# drv.net
KiCad netlist of a schematic drawn in Altium Designer
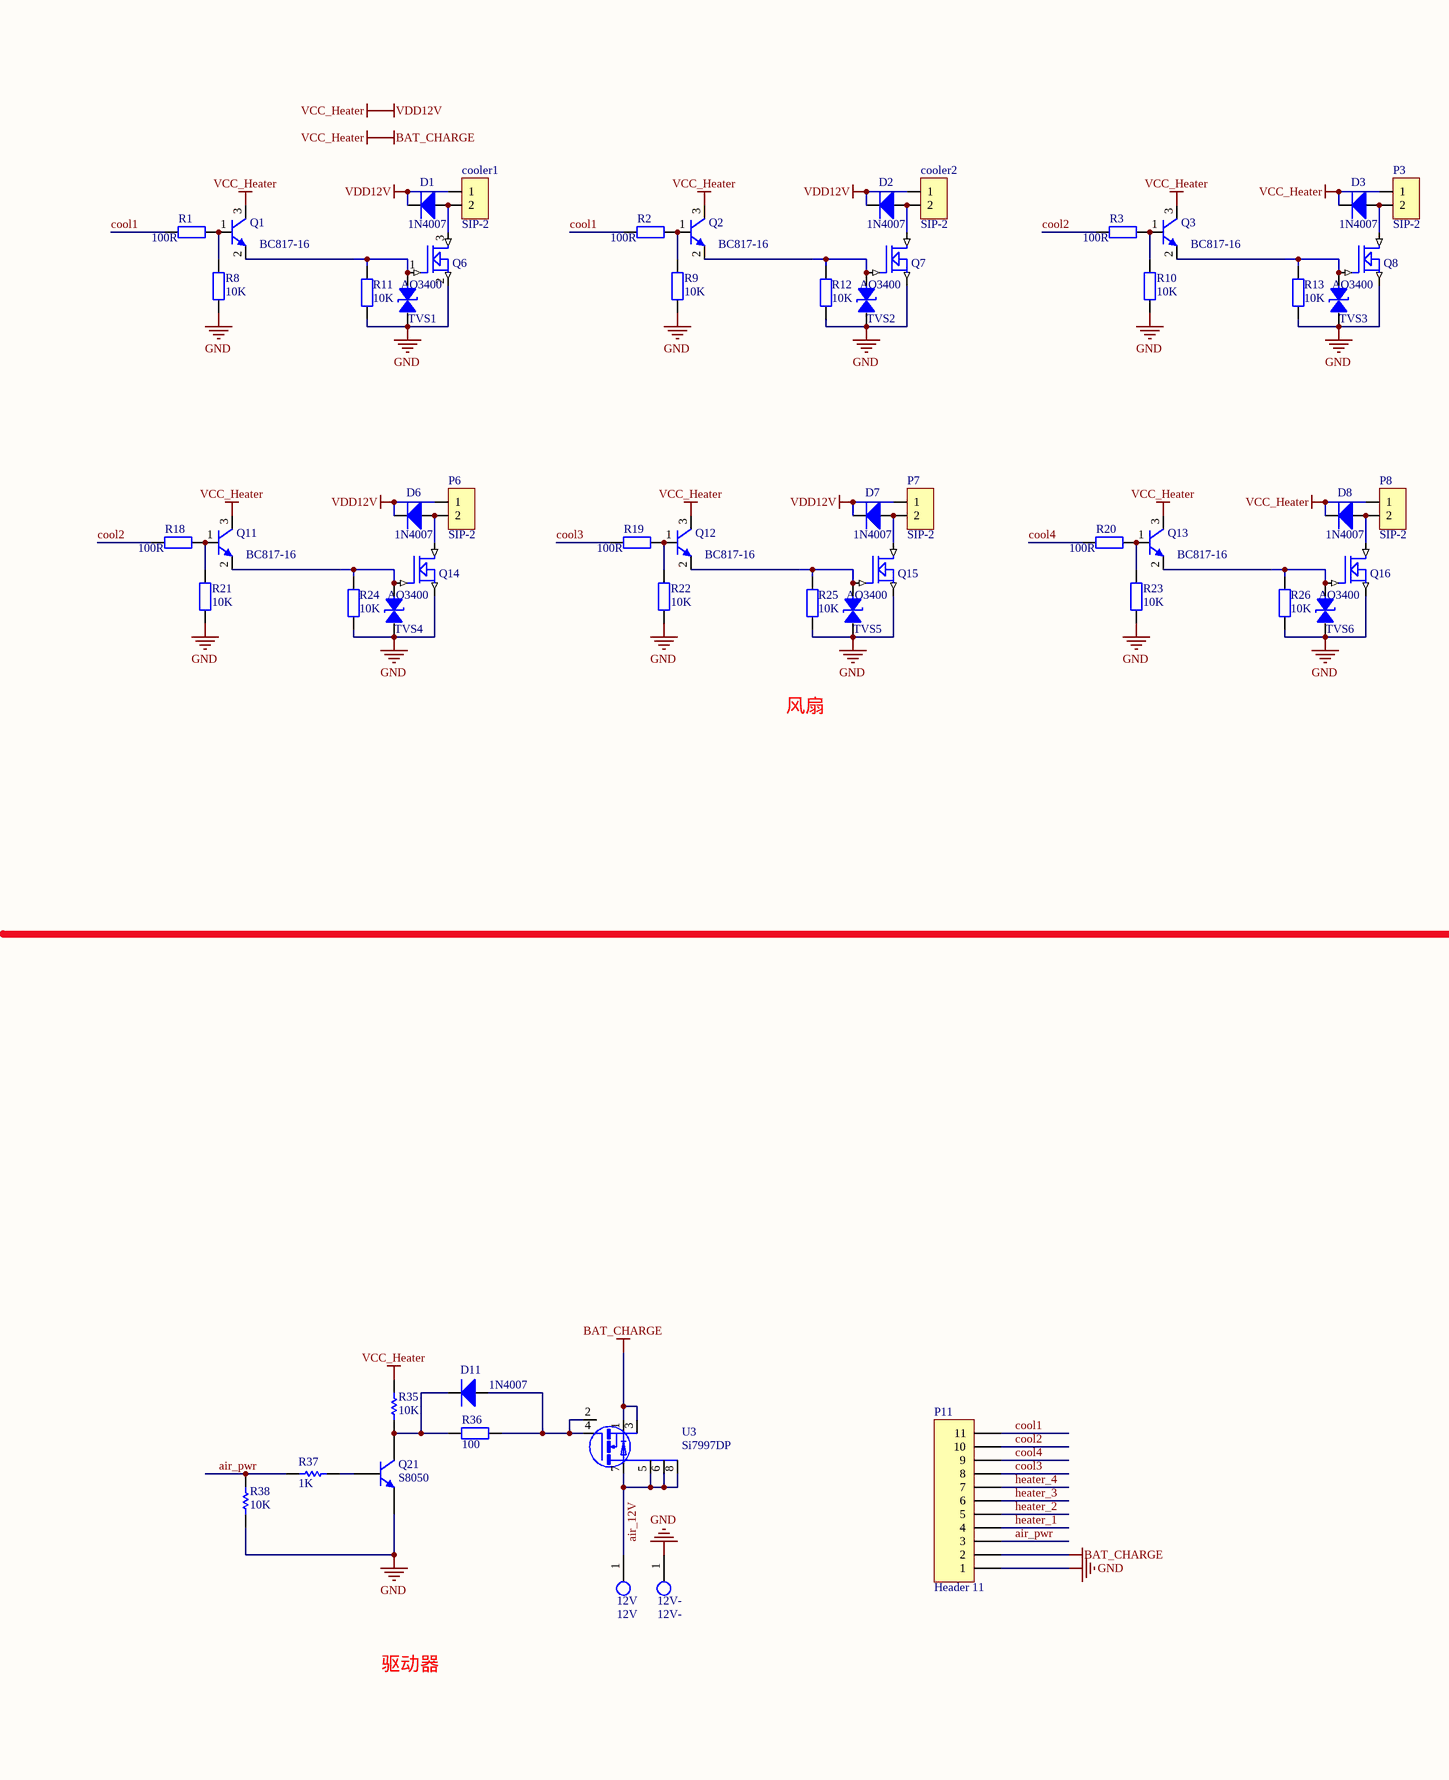
[diagram p0: drv.SchDoc, left]
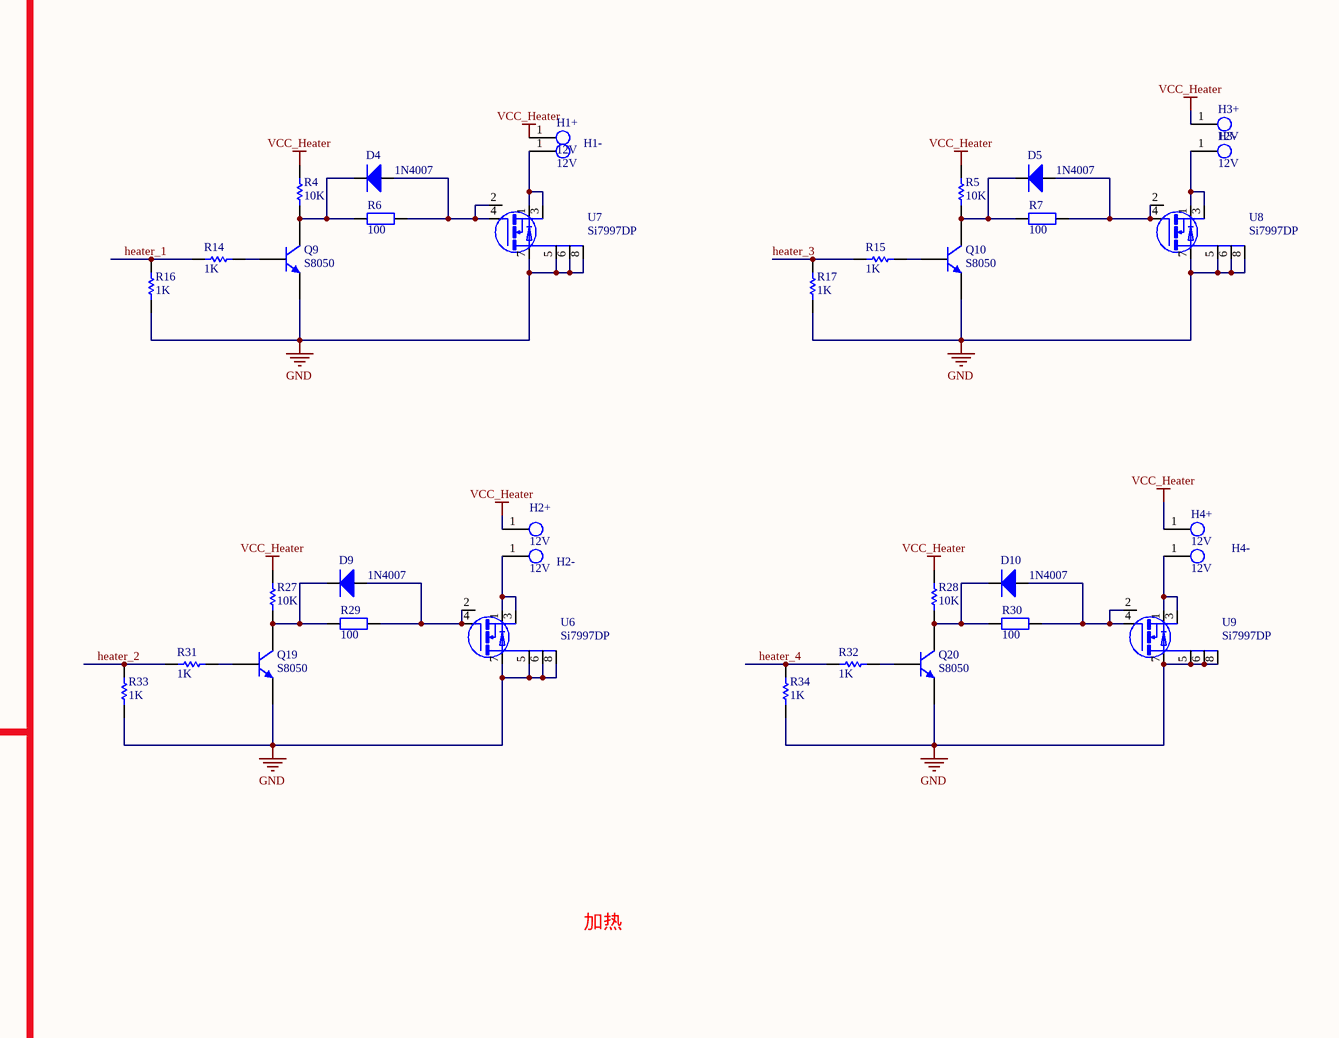
[diagram p1: drv.SchDoc, right]

(export (version "E")
  (design (tool "Eeschema 10.0.6"))
  (components
    (comp (ref "12V") (value "12V") (footprint "FIX-4.5") (libsource (lib "Schlib_20110825") (part "TP")))
    (comp (ref "12V-") (value "12V-") (footprint "FIX-4.5") (libsource (lib "Schlib_20110825") (part "TP")))
    (comp (ref "cooler1")
      (value "SIP-2")
      (footprint "SIP-2A")
      (description "XH2.54 2P 立贴")
      (libsource (lib "XiaoyI") (part "SIP-2"))
    )
    (comp (ref "cooler2")
      (value "SIP-2")
      (footprint "SIP-2A")
      (description "XH2.54 2P 立贴")
      (libsource (lib "XiaoyI") (part "SIP-2"))
    )
    (comp (ref "D1")
      (value "1N4007")
      (footprint "DO-214-AC")
      (description "贴片二极管")
      (libsource (lib "XiaoyI") (part "DIODE2"))
    )
    (comp (ref "D2")
      (value "1N4007")
      (footprint "DO-214-AC")
      (description "贴片二极管")
      (libsource (lib "XiaoyI") (part "DIODE2"))
    )
    (comp (ref "D3")
      (value "1N4007")
      (footprint "DO-214-AC")
      (description "贴片二极管")
      (libsource (lib "XiaoyI") (part "DIODE2"))
    )
    (comp (ref "D4")
      (value "1N4007")
      (footprint "DO-214-AC")
      (description "贴片二极管")
      (libsource (lib "XiaoyI") (part "DIODE2"))
    )
    (comp (ref "D5")
      (value "1N4007")
      (footprint "DO-214-AC")
      (description "贴片二极管")
      (libsource (lib "XiaoyI") (part "DIODE2"))
    )
    (comp (ref "D6")
      (value "1N4007")
      (footprint "DO-214-AC")
      (description "贴片二极管")
      (libsource (lib "XiaoyI") (part "DIODE2"))
    )
    (comp (ref "D7")
      (value "1N4007")
      (footprint "DO-214-AC")
      (description "贴片二极管")
      (libsource (lib "XiaoyI") (part "DIODE2"))
    )
    (comp (ref "D8")
      (value "1N4007")
      (footprint "DO-214-AC")
      (description "贴片二极管")
      (libsource (lib "XiaoyI") (part "DIODE2"))
    )
    (comp (ref "D9")
      (value "1N4007")
      (footprint "DO-214-AC")
      (description "贴片二极管")
      (libsource (lib "XiaoyI") (part "DIODE2"))
    )
    (comp (ref "D10")
      (value "1N4007")
      (footprint "DO-214-AC")
      (description "贴片二极管")
      (libsource (lib "XiaoyI") (part "DIODE2"))
    )
    (comp (ref "D11")
      (value "1N4007")
      (footprint "DO-214-AC")
      (description "贴片二极管")
      (libsource (lib "XiaoyI") (part "DIODE2"))
    )
    (comp (ref "H1+") (value "12V") (footprint "FIX-4.5") (libsource (lib "Schlib_20110825") (part "TP")))
    (comp (ref "H1-") (value "12V") (footprint "FIX-4.5") (libsource (lib "Schlib_20110825") (part "TP")))
    (comp (ref "H2+") (value "12V") (footprint "FIX-4.5") (libsource (lib "Schlib_20110825") (part "TP")))
    (comp (ref "H2-") (value "12V") (footprint "FIX-4.5") (libsource (lib "Schlib_20110825") (part "TP")))
    (comp (ref "H3+") (value "12V") (footprint "FIX-4.5") (libsource (lib "Schlib_20110825") (part "TP")))
    (comp (ref "H3-") (value "12V") (footprint "FIX-4.5") (libsource (lib "Schlib_20110825") (part "TP")))
    (comp (ref "H4+") (value "12V") (footprint "FIX-4.5") (libsource (lib "Schlib_20110825") (part "TP")))
    (comp (ref "H4-") (value "12V") (footprint "FIX-4.5") (libsource (lib "Schlib_20110825") (part "TP")))
    (comp (ref "P3")
      (value "SIP-2")
      (footprint "SIP-2A")
      (description "XH2.54 2P 立贴")
      (libsource (lib "XiaoyI") (part "SIP-2"))
    )
    (comp (ref "P6")
      (value "SIP-2")
      (footprint "SIP-2A")
      (description "XH2.54 2P 立贴")
      (libsource (lib "XiaoyI") (part "SIP-2"))
    )
    (comp (ref "P7")
      (value "SIP-2")
      (footprint "SIP-2A")
      (description "XH2.54 2P 立贴")
      (libsource (lib "XiaoyI") (part "SIP-2"))
    )
    (comp (ref "P8")
      (value "SIP-2")
      (footprint "SIP-2A")
      (description "XH2.54 2P 立贴")
      (libsource (lib "XiaoyI") (part "SIP-2"))
    )
    (comp (ref "P11")
      (value "Header 11")
      (footprint "12X2MMZ")
      (description "Header, 11-Pin")
      (fields (field (name "PUBLISHER") "Altium Limited"))
      (libsource (lib "Miscellaneous Connectors") (part "Header 11"))
    )
    (comp (ref "Q1")
      (value "BC817-16")
      (footprint "SOT23-3")
      (description "三极管")
      (libsource (lib "XiaoyI") (part "NPN-1"))
    )
    (comp (ref "Q2")
      (value "BC817-16")
      (footprint "SOT23-3")
      (description "三极管")
      (libsource (lib "XiaoyI") (part "NPN-1"))
    )
    (comp (ref "Q3")
      (value "BC817-16")
      (footprint "SOT23-3")
      (description "三极管")
      (libsource (lib "XiaoyI") (part "NPN-1"))
    )
    (comp (ref "Q6")
      (value "AO3400")
      (footprint "SOT23-3")
      (description "MOSFET N")
      (libsource (lib "") (part "MOSFET N_1"))
    )
    (comp (ref "Q7")
      (value "AO3400")
      (footprint "SOT23-3")
      (description "MOSFET N")
      (libsource (lib "XiaoyI") (part "MOSFET N"))
    )
    (comp (ref "Q8")
      (value "AO3400")
      (footprint "SOT23-3")
      (description "MOSFET N")
      (libsource (lib "XiaoyI") (part "MOSFET N"))
    )
    (comp (ref "Q9")
      (value "S8050")
      (footprint "SOT23-3")
      (description "NPN Bipolar Transistor")
      (fields (field (name "PUBLISHER") "Altium Limited"))
      (libsource (lib "Miscellaneous Devices") (part "NPN"))
    )
    (comp (ref "Q10")
      (value "S8050")
      (footprint "SOT23-3")
      (description "NPN Bipolar Transistor")
      (fields (field (name "PUBLISHER") "Altium Limited"))
      (libsource (lib "Miscellaneous Devices") (part "NPN"))
    )
    (comp (ref "Q11")
      (value "BC817-16")
      (footprint "SOT23-3")
      (description "三极管")
      (libsource (lib "XiaoyI") (part "NPN-1"))
    )
    (comp (ref "Q12")
      (value "BC817-16")
      (footprint "SOT23-3")
      (description "三极管")
      (libsource (lib "XiaoyI") (part "NPN-1"))
    )
    (comp (ref "Q13")
      (value "BC817-16")
      (footprint "SOT23-3")
      (description "三极管")
      (libsource (lib "XiaoyI") (part "NPN-1"))
    )
    (comp (ref "Q14")
      (value "AO3400")
      (footprint "SOT23-3")
      (description "MOSFET N")
      (libsource (lib "XiaoyI") (part "MOSFET N"))
    )
    (comp (ref "Q15")
      (value "AO3400")
      (footprint "SOT23-3")
      (description "MOSFET N")
      (libsource (lib "XiaoyI") (part "MOSFET N"))
    )
    (comp (ref "Q16")
      (value "AO3400")
      (footprint "SOT23-3")
      (description "MOSFET N")
      (libsource (lib "XiaoyI") (part "MOSFET N"))
    )
    (comp (ref "Q19")
      (value "S8050")
      (footprint "SOT23-3")
      (description "NPN Bipolar Transistor")
      (fields (field (name "PUBLISHER") "Altium Limited"))
      (libsource (lib "Miscellaneous Devices") (part "NPN"))
    )
    (comp (ref "Q20")
      (value "S8050")
      (footprint "SOT23-3")
      (description "NPN Bipolar Transistor")
      (fields (field (name "PUBLISHER") "Altium Limited"))
      (libsource (lib "Miscellaneous Devices") (part "NPN"))
    )
    (comp (ref "Q21")
      (value "S8050")
      (footprint "SOT23-3")
      (description "NPN Bipolar Transistor")
      (fields (field (name "PUBLISHER") "Altium Limited"))
      (libsource (lib "Miscellaneous Devices") (part "NPN"))
    )
    (comp (ref "R1")
      (value "100R")
      (footprint "0603R")
      (description "贴片电阻 5%")
      (libsource (lib "XiaoyI") (part "RES-SOP"))
    )
    (comp (ref "R2")
      (value "100R")
      (footprint "0603R")
      (description "贴片电阻 5%")
      (libsource (lib "XiaoyI") (part "RES-SOP"))
    )
    (comp (ref "R3")
      (value "100R")
      (footprint "0603R")
      (description "贴片电阻 5%")
      (libsource (lib "XiaoyI") (part "RES-SOP"))
    )
    (comp (ref "R4")
      (value "10K")
      (footprint "0603R")
      (description "Resistor")
      (fields (field (name "PUBLISHER") "Altium Limited"))
      (libsource (lib "Miscellaneous Devices") (part "Res1"))
    )
    (comp (ref "R5")
      (value "10K")
      (footprint "0603R")
      (description "Resistor")
      (fields (field (name "PUBLISHER") "Altium Limited"))
      (libsource (lib "Miscellaneous Devices") (part "Res1"))
    )
    (comp (ref "R6")
      (value "100")
      (footprint "0603R")
      (description "贴片电阻 5%")
      (libsource (lib "") (part "RES-SOP_1"))
    )
    (comp (ref "R7")
      (value "100")
      (footprint "0603R")
      (description "贴片电阻 5%")
      (libsource (lib "") (part "RES-SOP_1"))
    )
    (comp (ref "R8")
      (value "10K")
      (footprint "0603R")
      (description "贴片电阻 5%")
      (libsource (lib "") (part "RES-SOP_3"))
    )
    (comp (ref "R9")
      (value "10K")
      (footprint "0603R")
      (description "贴片电阻 5%")
      (libsource (lib "") (part "RES-SOP_3"))
    )
    (comp (ref "R10")
      (value "10K")
      (footprint "0603R")
      (description "贴片电阻 5%")
      (libsource (lib "") (part "RES-SOP_3"))
    )
    (comp (ref "R11")
      (value "10K")
      (footprint "0603R")
      (description "贴片电阻 5%")
      (libsource (lib "") (part "RES-SOP_2"))
    )
    (comp (ref "R12")
      (value "10K")
      (footprint "0603R")
      (description "贴片电阻 5%")
      (libsource (lib "") (part "RES-SOP_2"))
    )
    (comp (ref "R13")
      (value "10K")
      (footprint "0603R")
      (description "贴片电阻 5%")
      (libsource (lib "") (part "RES-SOP_2"))
    )
    (comp (ref "R14")
      (value "1K")
      (footprint "0603R")
      (description "Resistor")
      (fields (field (name "PUBLISHER") "Altium Limited"))
      (libsource (lib "Miscellaneous Devices") (part "Res1"))
    )
    (comp (ref "R15")
      (value "1K")
      (footprint "0603R")
      (description "Resistor")
      (fields (field (name "PUBLISHER") "Altium Limited"))
      (libsource (lib "Miscellaneous Devices") (part "Res1"))
    )
    (comp (ref "R16")
      (value "1K")
      (footprint "0603R")
      (description "Resistor")
      (fields (field (name "PUBLISHER") "Altium Limited"))
      (libsource (lib "Miscellaneous Devices") (part "Res1"))
    )
    (comp (ref "R17")
      (value "1K")
      (footprint "0603R")
      (description "Resistor")
      (fields (field (name "PUBLISHER") "Altium Limited"))
      (libsource (lib "Miscellaneous Devices") (part "Res1"))
    )
    (comp (ref "R18")
      (value "100R")
      (footprint "0603R")
      (description "贴片电阻 5%")
      (libsource (lib "XiaoyI") (part "RES-SOP"))
    )
    (comp (ref "R19")
      (value "100R")
      (footprint "0603R")
      (description "贴片电阻 5%")
      (libsource (lib "XiaoyI") (part "RES-SOP"))
    )
    (comp (ref "R20")
      (value "100R")
      (footprint "0603R")
      (description "贴片电阻 5%")
      (libsource (lib "XiaoyI") (part "RES-SOP"))
    )
    (comp (ref "R21")
      (value "10K")
      (footprint "0603R")
      (description "贴片电阻 5%")
      (libsource (lib "") (part "RES-SOP_3"))
    )
    (comp (ref "R22")
      (value "10K")
      (footprint "0603R")
      (description "贴片电阻 5%")
      (libsource (lib "") (part "RES-SOP_3"))
    )
    (comp (ref "R23")
      (value "10K")
      (footprint "0603R")
      (description "贴片电阻 5%")
      (libsource (lib "") (part "RES-SOP_3"))
    )
    (comp (ref "R24")
      (value "10K")
      (footprint "0603R")
      (description "贴片电阻 5%")
      (libsource (lib "") (part "RES-SOP_2"))
    )
    (comp (ref "R25")
      (value "10K")
      (footprint "0603R")
      (description "贴片电阻 5%")
      (libsource (lib "") (part "RES-SOP_2"))
    )
    (comp (ref "R26")
      (value "10K")
      (footprint "0603R")
      (description "贴片电阻 5%")
      (libsource (lib "") (part "RES-SOP_2"))
    )
    (comp (ref "R27")
      (value "10K")
      (footprint "0603R")
      (description "Resistor")
      (fields (field (name "PUBLISHER") "Altium Limited"))
      (libsource (lib "Miscellaneous Devices") (part "Res1"))
    )
    (comp (ref "R28")
      (value "10K")
      (footprint "0603R")
      (description "Resistor")
      (fields (field (name "PUBLISHER") "Altium Limited"))
      (libsource (lib "Miscellaneous Devices") (part "Res1"))
    )
    (comp (ref "R29")
      (value "100")
      (footprint "0603R")
      (description "贴片电阻 5%")
      (libsource (lib "") (part "RES-SOP_1"))
    )
    (comp (ref "R30")
      (value "100")
      (footprint "0603R")
      (description "贴片电阻 5%")
      (libsource (lib "") (part "RES-SOP_1"))
    )
    (comp (ref "R31")
      (value "1K")
      (footprint "0603R")
      (description "Resistor")
      (fields (field (name "PUBLISHER") "Altium Limited"))
      (libsource (lib "Miscellaneous Devices") (part "Res1"))
    )
    (comp (ref "R32")
      (value "1K")
      (footprint "0603R")
      (description "Resistor")
      (fields (field (name "PUBLISHER") "Altium Limited"))
      (libsource (lib "Miscellaneous Devices") (part "Res1"))
    )
    (comp (ref "R33")
      (value "1K")
      (footprint "0603R")
      (description "Resistor")
      (fields (field (name "PUBLISHER") "Altium Limited"))
      (libsource (lib "Miscellaneous Devices") (part "Res1"))
    )
    (comp (ref "R34")
      (value "1K")
      (footprint "0603R")
      (description "Resistor")
      (fields (field (name "PUBLISHER") "Altium Limited"))
      (libsource (lib "Miscellaneous Devices") (part "Res1"))
    )
    (comp (ref "R35")
      (value "10K")
      (footprint "0603R")
      (description "Resistor")
      (fields (field (name "PUBLISHER") "Altium Limited"))
      (libsource (lib "Miscellaneous Devices") (part "Res1"))
    )
    (comp (ref "R36")
      (value "100")
      (footprint "0603R")
      (description "贴片电阻 5%")
      (libsource (lib "") (part "RES-SOP_1"))
    )
    (comp (ref "R37")
      (value "1K")
      (footprint "0603R")
      (description "Resistor")
      (fields (field (name "PUBLISHER") "Altium Limited"))
      (libsource (lib "Miscellaneous Devices") (part "Res1"))
    )
    (comp (ref "R38")
      (value "10K")
      (footprint "0603R")
      (description "Resistor")
      (fields (field (name "PUBLISHER") "Altium Limited"))
      (libsource (lib "Miscellaneous Devices") (part "Res1"))
    )
    (comp (ref "TVS1")
      (value "ESD5Z5.0CT1G")
      (footprint "SOD-523")
      (description "TVS")
      (libsource (lib "XiaoyI") (part "TVS-1"))
    )
    (comp (ref "TVS2")
      (value "ESD5Z5.0CT1G")
      (footprint "SOD-523")
      (description "TVS")
      (libsource (lib "XiaoyI") (part "TVS-1"))
    )
    (comp (ref "TVS3")
      (value "ESD5Z5.0CT1G")
      (footprint "SOD-523")
      (description "TVS")
      (libsource (lib "XiaoyI") (part "TVS-1"))
    )
    (comp (ref "TVS4")
      (value "ESD5Z5.0CT1G")
      (footprint "SOD-523")
      (description "TVS")
      (libsource (lib "XiaoyI") (part "TVS-1"))
    )
    (comp (ref "TVS5")
      (value "ESD5Z5.0CT1G")
      (footprint "SOD-523")
      (description "TVS")
      (libsource (lib "XiaoyI") (part "TVS-1"))
    )
    (comp (ref "TVS6")
      (value "ESD5Z5.0CT1G")
      (footprint "SOD-523")
      (description "TVS")
      (libsource (lib "XiaoyI") (part "TVS-1"))
    )
    (comp (ref "U3")
      (value "Si7997DP")
      (footprint "PowerPAK SO-8")
      (description "Sia430DJ")
      (libsource (lib "Schlib_20110825") (part "Si7997DP"))
    )
    (comp (ref "U6")
      (value "Si7997DP")
      (footprint "PowerPAK SO-8")
      (description "Sia430DJ")
      (libsource (lib "Schlib_20110825") (part "Si7997DP"))
    )
    (comp (ref "U7")
      (value "Si7997DP")
      (footprint "PowerPAK SO-8")
      (description "Sia430DJ")
      (libsource (lib "Schlib_20110825") (part "Si7997DP"))
    )
    (comp (ref "U8")
      (value "Si7997DP")
      (footprint "PowerPAK SO-8")
      (description "Sia430DJ")
      (libsource (lib "Schlib_20110825") (part "Si7997DP"))
    )
    (comp (ref "U9")
      (value "Si7997DP")
      (footprint "PowerPAK SO-8")
      (description "Sia430DJ")
      (libsource (lib "Schlib_20110825") (part "Si7997DP"))
    )
  )
  (nets
    (net (code "1") (name "/air_12V") (class "Default")
      (node (ref "12V") (pin "1") (pintype "passive"))
      (node (ref "U3") (pin "5") (pinfunction "D_5") (pintype "passive"))
      (node (ref "U3") (pin "6") (pinfunction "D_6") (pintype "passive"))
      (node (ref "U3") (pin "7") (pinfunction "D_7") (pintype "passive"))
      (node (ref "U3") (pin "8") (pinfunction "D_8") (pintype "passive"))
    )
    (net (code "2") (name "/air_pwr") (class "Default")
      (node (ref "P11") (pin "3") (pinfunction "3_3") (pintype "passive"))
      (node (ref "R37") (pin "2") (pinfunction "2_2") (pintype "passive"))
      (node (ref "R38") (pin "1") (pinfunction "1_1") (pintype "passive"))
    )
    (net (code "3") (name "/cool1") (class "Default")
      (node (ref "P11") (pin "11") (pinfunction "11_11") (pintype "passive"))
      (node (ref "R1") (pin "2") (pinfunction "2_2") (pintype "passive"))
      (node (ref "R2") (pin "2") (pinfunction "2_2") (pintype "passive"))
    )
    (net (code "4") (name "/cool2") (class "Default")
      (node (ref "P11") (pin "10") (pinfunction "10_10") (pintype "passive"))
      (node (ref "R18") (pin "2") (pinfunction "2_2") (pintype "passive"))
      (node (ref "R3") (pin "2") (pinfunction "2_2") (pintype "passive"))
    )
    (net (code "5") (name "/cool3") (class "Default")
      (node (ref "P11") (pin "8") (pinfunction "8_8") (pintype "passive"))
      (node (ref "R19") (pin "2") (pinfunction "2_2") (pintype "passive"))
    )
    (net (code "6") (name "/cool4") (class "Default")
      (node (ref "P11") (pin "9") (pinfunction "9_9") (pintype "passive"))
      (node (ref "R20") (pin "2") (pinfunction "2_2") (pintype "passive"))
    )
    (net (code "7") (name "/heater_1") (class "Default")
      (node (ref "P11") (pin "4") (pinfunction "4_4") (pintype "passive"))
      (node (ref "R14") (pin "2") (pinfunction "2_2") (pintype "passive"))
      (node (ref "R16") (pin "1") (pinfunction "1_1") (pintype "passive"))
    )
    (net (code "8") (name "/heater_2") (class "Default")
      (node (ref "P11") (pin "5") (pinfunction "5_5") (pintype "passive"))
      (node (ref "R31") (pin "2") (pinfunction "2_2") (pintype "passive"))
      (node (ref "R33") (pin "1") (pinfunction "1_1") (pintype "passive"))
    )
    (net (code "9") (name "/heater_3") (class "Default")
      (node (ref "P11") (pin "6") (pinfunction "6_6") (pintype "passive"))
      (node (ref "R15") (pin "2") (pinfunction "2_2") (pintype "passive"))
      (node (ref "R17") (pin "1") (pinfunction "1_1") (pintype "passive"))
    )
    (net (code "10") (name "/heater_4") (class "Default")
      (node (ref "P11") (pin "7") (pinfunction "7_7") (pintype "passive"))
      (node (ref "R32") (pin "2") (pinfunction "2_2") (pintype "passive"))
      (node (ref "R34") (pin "1") (pinfunction "1_1") (pintype "passive"))
    )
    (net (code "11") (name "BAT_CHARGE") (class "Default")
      (node (ref "D1") (pin "2") (pinfunction "K_2") (pintype "passive"))
      (node (ref "D2") (pin "2") (pinfunction "K_2") (pintype "passive"))
      (node (ref "D3") (pin "2") (pinfunction "K_2") (pintype "passive"))
      (node (ref "D6") (pin "2") (pinfunction "K_2") (pintype "passive"))
      (node (ref "D7") (pin "2") (pinfunction "K_2") (pintype "passive"))
      (node (ref "D8") (pin "2") (pinfunction "K_2") (pintype "passive"))
      (node (ref "H1+") (pin "1") (pintype "passive"))
      (node (ref "H2+") (pin "1") (pintype "passive"))
      (node (ref "H3+") (pin "1") (pintype "passive"))
      (node (ref "H4+") (pin "1") (pintype "passive"))
      (node (ref "P11") (pin "2") (pinfunction "2_2") (pintype "passive"))
      (node (ref "P3") (pin "1") (pinfunction "1_1") (pintype "passive"))
      (node (ref "P6") (pin "1") (pinfunction "1_1") (pintype "passive"))
      (node (ref "P7") (pin "1") (pinfunction "1_1") (pintype "passive"))
      (node (ref "P8") (pin "1") (pinfunction "1_1") (pintype "passive"))
      (node (ref "Q1") (pin "3") (pinfunction "C_3") (pintype "passive"))
      (node (ref "Q11") (pin "3") (pinfunction "C_3") (pintype "passive"))
      (node (ref "Q12") (pin "3") (pinfunction "C_3") (pintype "passive"))
      (node (ref "Q13") (pin "3") (pinfunction "C_3") (pintype "passive"))
      (node (ref "Q2") (pin "3") (pinfunction "C_3") (pintype "passive"))
      (node (ref "Q3") (pin "3") (pinfunction "C_3") (pintype "passive"))
      (node (ref "R27") (pin "2") (pinfunction "2_2") (pintype "passive"))
      (node (ref "R28") (pin "2") (pinfunction "2_2") (pintype "passive"))
      (node (ref "R35") (pin "2") (pinfunction "2_2") (pintype "passive"))
      (node (ref "R4") (pin "2") (pinfunction "2_2") (pintype "passive"))
      (node (ref "R5") (pin "2") (pinfunction "2_2") (pintype "passive"))
      (node (ref "U3") (pin "1") (pinfunction "S_1") (pintype "passive"))
      (node (ref "U3") (pin "3") (pinfunction "S_3") (pintype "passive"))
      (node (ref "cooler1") (pin "1") (pinfunction "1_1") (pintype "passive"))
      (node (ref "cooler2") (pin "1") (pinfunction "1_1") (pintype "passive"))
    )
    (net (code "12") (name "GND") (class "Default")
      (node (ref "12V-") (pin "1") (pintype "passive"))
      (node (ref "P11") (pin "1") (pinfunction "1_1") (pintype "passive"))
      (node (ref "Q10") (pin "2") (pinfunction "E_2") (pintype "passive"))
      (node (ref "Q14") (pin "2") (pinfunction "S_2") (pintype "output"))
      (node (ref "Q15") (pin "2") (pinfunction "S_2") (pintype "output"))
      (node (ref "Q16") (pin "2") (pinfunction "S_2") (pintype "output"))
      (node (ref "Q19") (pin "2") (pinfunction "E_2") (pintype "passive"))
      (node (ref "Q20") (pin "2") (pinfunction "E_2") (pintype "passive"))
      (node (ref "Q21") (pin "2") (pinfunction "E_2") (pintype "passive"))
      (node (ref "Q6") (pin "2") (pinfunction "S_2") (pintype "output"))
      (node (ref "Q7") (pin "2") (pinfunction "S_2") (pintype "output"))
      (node (ref "Q8") (pin "2") (pinfunction "S_2") (pintype "output"))
      (node (ref "Q9") (pin "2") (pinfunction "E_2") (pintype "passive"))
      (node (ref "R10") (pin "1") (pinfunction "1_1") (pintype "passive"))
      (node (ref "R11") (pin "2") (pinfunction "2_2") (pintype "passive"))
      (node (ref "R12") (pin "2") (pinfunction "2_2") (pintype "passive"))
      (node (ref "R13") (pin "2") (pinfunction "2_2") (pintype "passive"))
      (node (ref "R16") (pin "2") (pinfunction "2_2") (pintype "passive"))
      (node (ref "R17") (pin "2") (pinfunction "2_2") (pintype "passive"))
      (node (ref "R21") (pin "1") (pinfunction "1_1") (pintype "passive"))
      (node (ref "R22") (pin "1") (pinfunction "1_1") (pintype "passive"))
      (node (ref "R23") (pin "1") (pinfunction "1_1") (pintype "passive"))
      (node (ref "R24") (pin "2") (pinfunction "2_2") (pintype "passive"))
      (node (ref "R25") (pin "2") (pinfunction "2_2") (pintype "passive"))
      (node (ref "R26") (pin "2") (pinfunction "2_2") (pintype "passive"))
      (node (ref "R33") (pin "2") (pinfunction "2_2") (pintype "passive"))
      (node (ref "R34") (pin "2") (pinfunction "2_2") (pintype "passive"))
      (node (ref "R38") (pin "2") (pinfunction "2_2") (pintype "passive"))
      (node (ref "R8") (pin "1") (pinfunction "1_1") (pintype "passive"))
      (node (ref "R9") (pin "1") (pinfunction "1_1") (pintype "passive"))
      (node (ref "TVS1") (pin "1") (pinfunction "A_1") (pintype "passive"))
      (node (ref "TVS2") (pin "1") (pinfunction "A_1") (pintype "passive"))
      (node (ref "TVS3") (pin "1") (pinfunction "A_1") (pintype "passive"))
      (node (ref "TVS4") (pin "1") (pinfunction "A_1") (pintype "passive"))
      (node (ref "TVS5") (pin "1") (pinfunction "A_1") (pintype "passive"))
      (node (ref "TVS6") (pin "1") (pinfunction "A_1") (pintype "passive"))
      (node (ref "U6") (pin "5") (pinfunction "D_5") (pintype "passive"))
      (node (ref "U6") (pin "6") (pinfunction "D_6") (pintype "passive"))
      (node (ref "U6") (pin "7") (pinfunction "D_7") (pintype "passive"))
      (node (ref "U6") (pin "8") (pinfunction "D_8") (pintype "passive"))
      (node (ref "U7") (pin "5") (pinfunction "D_5") (pintype "passive"))
      (node (ref "U7") (pin "6") (pinfunction "D_6") (pintype "passive"))
      (node (ref "U7") (pin "7") (pinfunction "D_7") (pintype "passive"))
      (node (ref "U7") (pin "8") (pinfunction "D_8") (pintype "passive"))
      (node (ref "U8") (pin "5") (pinfunction "D_5") (pintype "passive"))
      (node (ref "U8") (pin "6") (pinfunction "D_6") (pintype "passive"))
      (node (ref "U8") (pin "7") (pinfunction "D_7") (pintype "passive"))
      (node (ref "U8") (pin "8") (pinfunction "D_8") (pintype "passive"))
      (node (ref "U9") (pin "5") (pinfunction "D_5") (pintype "passive"))
      (node (ref "U9") (pin "6") (pinfunction "D_6") (pintype "passive"))
      (node (ref "U9") (pin "7") (pinfunction "D_7") (pintype "passive"))
      (node (ref "U9") (pin "8") (pinfunction "D_8") (pintype "passive"))
    )
    (net (code "13") (name "Net-(D1-A)") (class "Default")
      (node (ref "D1") (pin "1") (pinfunction "A_1") (pintype "passive"))
      (node (ref "Q6") (pin "3") (pinfunction "D_3") (pintype "input"))
      (node (ref "cooler1") (pin "2") (pinfunction "2_2") (pintype "passive"))
    )
    (net (code "14") (name "Net-(D2-A)") (class "Default")
      (node (ref "D2") (pin "1") (pinfunction "A_1") (pintype "passive"))
      (node (ref "Q7") (pin "3") (pinfunction "D_3") (pintype "input"))
      (node (ref "cooler2") (pin "2") (pinfunction "2_2") (pintype "passive"))
    )
    (net (code "15") (name "Net-(D3-A)") (class "Default")
      (node (ref "D3") (pin "1") (pinfunction "A_1") (pintype "passive"))
      (node (ref "P3") (pin "2") (pinfunction "2_2") (pintype "passive"))
      (node (ref "Q8") (pin "3") (pinfunction "D_3") (pintype "input"))
    )
    (net (code "16") (name "Net-(D4-A)") (class "Default")
      (node (ref "D4") (pin "1") (pinfunction "A_1") (pintype "passive"))
      (node (ref "R6") (pin "2") (pinfunction "2_2") (pintype "passive"))
      (node (ref "U7") (pin "2") (pinfunction "G_2") (pintype "passive"))
      (node (ref "U7") (pin "4") (pinfunction "G_4") (pintype "passive"))
    )
    (net (code "17") (name "Net-(D4-K)") (class "Default")
      (node (ref "D4") (pin "2") (pinfunction "K_2") (pintype "passive"))
      (node (ref "Q9") (pin "3") (pinfunction "C_3") (pintype "passive"))
      (node (ref "R4") (pin "1") (pinfunction "1_1") (pintype "passive"))
      (node (ref "R6") (pin "1") (pinfunction "1_1") (pintype "passive"))
    )
    (net (code "18") (name "Net-(D5-A)") (class "Default")
      (node (ref "D5") (pin "1") (pinfunction "A_1") (pintype "passive"))
      (node (ref "R7") (pin "2") (pinfunction "2_2") (pintype "passive"))
      (node (ref "U8") (pin "2") (pinfunction "G_2") (pintype "passive"))
      (node (ref "U8") (pin "4") (pinfunction "G_4") (pintype "passive"))
    )
    (net (code "19") (name "Net-(D5-K)") (class "Default")
      (node (ref "D5") (pin "2") (pinfunction "K_2") (pintype "passive"))
      (node (ref "Q10") (pin "3") (pinfunction "C_3") (pintype "passive"))
      (node (ref "R5") (pin "1") (pinfunction "1_1") (pintype "passive"))
      (node (ref "R7") (pin "1") (pinfunction "1_1") (pintype "passive"))
    )
    (net (code "20") (name "Net-(D6-A)") (class "Default")
      (node (ref "D6") (pin "1") (pinfunction "A_1") (pintype "passive"))
      (node (ref "P6") (pin "2") (pinfunction "2_2") (pintype "passive"))
      (node (ref "Q14") (pin "3") (pinfunction "D_3") (pintype "input"))
    )
    (net (code "21") (name "Net-(D7-A)") (class "Default")
      (node (ref "D7") (pin "1") (pinfunction "A_1") (pintype "passive"))
      (node (ref "P7") (pin "2") (pinfunction "2_2") (pintype "passive"))
      (node (ref "Q15") (pin "3") (pinfunction "D_3") (pintype "input"))
    )
    (net (code "22") (name "Net-(D8-A)") (class "Default")
      (node (ref "D8") (pin "1") (pinfunction "A_1") (pintype "passive"))
      (node (ref "P8") (pin "2") (pinfunction "2_2") (pintype "passive"))
      (node (ref "Q16") (pin "3") (pinfunction "D_3") (pintype "input"))
    )
    (net (code "23") (name "Net-(D9-A)") (class "Default")
      (node (ref "D9") (pin "1") (pinfunction "A_1") (pintype "passive"))
      (node (ref "R29") (pin "2") (pinfunction "2_2") (pintype "passive"))
      (node (ref "U6") (pin "2") (pinfunction "G_2") (pintype "passive"))
      (node (ref "U6") (pin "4") (pinfunction "G_4") (pintype "passive"))
    )
    (net (code "24") (name "Net-(D9-K)") (class "Default")
      (node (ref "D9") (pin "2") (pinfunction "K_2") (pintype "passive"))
      (node (ref "Q19") (pin "3") (pinfunction "C_3") (pintype "passive"))
      (node (ref "R27") (pin "1") (pinfunction "1_1") (pintype "passive"))
      (node (ref "R29") (pin "1") (pinfunction "1_1") (pintype "passive"))
    )
    (net (code "25") (name "Net-(D10-A)") (class "Default")
      (node (ref "D10") (pin "1") (pinfunction "A_1") (pintype "passive"))
      (node (ref "R30") (pin "2") (pinfunction "2_2") (pintype "passive"))
      (node (ref "U9") (pin "2") (pinfunction "G_2") (pintype "passive"))
      (node (ref "U9") (pin "4") (pinfunction "G_4") (pintype "passive"))
    )
    (net (code "26") (name "Net-(D10-K)") (class "Default")
      (node (ref "D10") (pin "2") (pinfunction "K_2") (pintype "passive"))
      (node (ref "Q20") (pin "3") (pinfunction "C_3") (pintype "passive"))
      (node (ref "R28") (pin "1") (pinfunction "1_1") (pintype "passive"))
      (node (ref "R30") (pin "1") (pinfunction "1_1") (pintype "passive"))
    )
    (net (code "27") (name "Net-(D11-A)") (class "Default")
      (node (ref "D11") (pin "1") (pinfunction "A_1") (pintype "passive"))
      (node (ref "R36") (pin "2") (pinfunction "2_2") (pintype "passive"))
      (node (ref "U3") (pin "2") (pinfunction "G_2") (pintype "passive"))
      (node (ref "U3") (pin "4") (pinfunction "G_4") (pintype "passive"))
    )
    (net (code "28") (name "Net-(D11-K)") (class "Default")
      (node (ref "D11") (pin "2") (pinfunction "K_2") (pintype "passive"))
      (node (ref "Q21") (pin "3") (pinfunction "C_3") (pintype "passive"))
      (node (ref "R35") (pin "1") (pinfunction "1_1") (pintype "passive"))
      (node (ref "R36") (pin "1") (pinfunction "1_1") (pintype "passive"))
    )
    (net (code "29") (name "Net-(H1--Pad1)") (class "Default")
      (node (ref "H1-") (pin "1") (pintype "passive"))
      (node (ref "U7") (pin "1") (pinfunction "S_1") (pintype "passive"))
      (node (ref "U7") (pin "3") (pinfunction "S_3") (pintype "passive"))
    )
    (net (code "30") (name "Net-(H2--Pad1)") (class "Default")
      (node (ref "H2-") (pin "1") (pintype "passive"))
      (node (ref "U6") (pin "1") (pinfunction "S_1") (pintype "passive"))
      (node (ref "U6") (pin "3") (pinfunction "S_3") (pintype "passive"))
    )
    (net (code "31") (name "Net-(H3--Pad1)") (class "Default")
      (node (ref "H3-") (pin "1") (pintype "passive"))
      (node (ref "U8") (pin "1") (pinfunction "S_1") (pintype "passive"))
      (node (ref "U8") (pin "3") (pinfunction "S_3") (pintype "passive"))
    )
    (net (code "32") (name "Net-(H4--Pad1)") (class "Default")
      (node (ref "H4-") (pin "1") (pintype "passive"))
      (node (ref "U9") (pin "1") (pinfunction "S_1") (pintype "passive"))
      (node (ref "U9") (pin "3") (pinfunction "S_3") (pintype "passive"))
    )
    (net (code "33") (name "Net-(Q1-B)") (class "Default")
      (node (ref "Q1") (pin "1") (pinfunction "B_1") (pintype "passive"))
      (node (ref "R1") (pin "1") (pinfunction "1_1") (pintype "passive"))
      (node (ref "R8") (pin "2") (pinfunction "2_2") (pintype "passive"))
    )
    (net (code "34") (name "Net-(Q1-E)") (class "Default")
      (node (ref "Q1") (pin "2") (pinfunction "E_2") (pintype "passive"))
      (node (ref "Q6") (pin "1") (pinfunction "G_1") (pintype "input"))
      (node (ref "R11") (pin "1") (pinfunction "1_1") (pintype "passive"))
      (node (ref "TVS1") (pin "2") (pinfunction "B_2") (pintype "passive"))
    )
    (net (code "35") (name "Net-(Q2-B)") (class "Default")
      (node (ref "Q2") (pin "1") (pinfunction "B_1") (pintype "passive"))
      (node (ref "R2") (pin "1") (pinfunction "1_1") (pintype "passive"))
      (node (ref "R9") (pin "2") (pinfunction "2_2") (pintype "passive"))
    )
    (net (code "36") (name "Net-(Q2-E)") (class "Default")
      (node (ref "Q2") (pin "2") (pinfunction "E_2") (pintype "passive"))
      (node (ref "Q7") (pin "1") (pinfunction "G_1") (pintype "input"))
      (node (ref "R12") (pin "1") (pinfunction "1_1") (pintype "passive"))
      (node (ref "TVS2") (pin "2") (pinfunction "B_2") (pintype "passive"))
    )
    (net (code "37") (name "Net-(Q3-B)") (class "Default")
      (node (ref "Q3") (pin "1") (pinfunction "B_1") (pintype "passive"))
      (node (ref "R10") (pin "2") (pinfunction "2_2") (pintype "passive"))
      (node (ref "R3") (pin "1") (pinfunction "1_1") (pintype "passive"))
    )
    (net (code "38") (name "Net-(Q3-E)") (class "Default")
      (node (ref "Q3") (pin "2") (pinfunction "E_2") (pintype "passive"))
      (node (ref "Q8") (pin "1") (pinfunction "G_1") (pintype "input"))
      (node (ref "R13") (pin "1") (pinfunction "1_1") (pintype "passive"))
      (node (ref "TVS3") (pin "2") (pinfunction "B_2") (pintype "passive"))
    )
    (net (code "39") (name "Net-(Q9-B)") (class "Default")
      (node (ref "Q9") (pin "1") (pinfunction "B_1") (pintype "passive"))
      (node (ref "R14") (pin "1") (pinfunction "1_1") (pintype "passive"))
    )
    (net (code "40") (name "Net-(Q10-B)") (class "Default")
      (node (ref "Q10") (pin "1") (pinfunction "B_1") (pintype "passive"))
      (node (ref "R15") (pin "1") (pinfunction "1_1") (pintype "passive"))
    )
    (net (code "41") (name "Net-(Q11-B)") (class "Default")
      (node (ref "Q11") (pin "1") (pinfunction "B_1") (pintype "passive"))
      (node (ref "R18") (pin "1") (pinfunction "1_1") (pintype "passive"))
      (node (ref "R21") (pin "2") (pinfunction "2_2") (pintype "passive"))
    )
    (net (code "42") (name "Net-(Q11-E)") (class "Default")
      (node (ref "Q11") (pin "2") (pinfunction "E_2") (pintype "passive"))
      (node (ref "Q14") (pin "1") (pinfunction "G_1") (pintype "input"))
      (node (ref "R24") (pin "1") (pinfunction "1_1") (pintype "passive"))
      (node (ref "TVS4") (pin "2") (pinfunction "B_2") (pintype "passive"))
    )
    (net (code "43") (name "Net-(Q12-B)") (class "Default")
      (node (ref "Q12") (pin "1") (pinfunction "B_1") (pintype "passive"))
      (node (ref "R19") (pin "1") (pinfunction "1_1") (pintype "passive"))
      (node (ref "R22") (pin "2") (pinfunction "2_2") (pintype "passive"))
    )
    (net (code "44") (name "Net-(Q12-E)") (class "Default")
      (node (ref "Q12") (pin "2") (pinfunction "E_2") (pintype "passive"))
      (node (ref "Q15") (pin "1") (pinfunction "G_1") (pintype "input"))
      (node (ref "R25") (pin "1") (pinfunction "1_1") (pintype "passive"))
      (node (ref "TVS5") (pin "2") (pinfunction "B_2") (pintype "passive"))
    )
    (net (code "45") (name "Net-(Q13-B)") (class "Default")
      (node (ref "Q13") (pin "1") (pinfunction "B_1") (pintype "passive"))
      (node (ref "R20") (pin "1") (pinfunction "1_1") (pintype "passive"))
      (node (ref "R23") (pin "2") (pinfunction "2_2") (pintype "passive"))
    )
    (net (code "46") (name "Net-(Q13-E)") (class "Default")
      (node (ref "Q13") (pin "2") (pinfunction "E_2") (pintype "passive"))
      (node (ref "Q16") (pin "1") (pinfunction "G_1") (pintype "input"))
      (node (ref "R26") (pin "1") (pinfunction "1_1") (pintype "passive"))
      (node (ref "TVS6") (pin "2") (pinfunction "B_2") (pintype "passive"))
    )
    (net (code "47") (name "Net-(Q19-B)") (class "Default")
      (node (ref "Q19") (pin "1") (pinfunction "B_1") (pintype "passive"))
      (node (ref "R31") (pin "1") (pinfunction "1_1") (pintype "passive"))
    )
    (net (code "48") (name "Net-(Q20-B)") (class "Default")
      (node (ref "Q20") (pin "1") (pinfunction "B_1") (pintype "passive"))
      (node (ref "R32") (pin "1") (pinfunction "1_1") (pintype "passive"))
    )
    (net (code "49") (name "Net-(Q21-B)") (class "Default")
      (node (ref "Q21") (pin "1") (pinfunction "B_1") (pintype "passive"))
      (node (ref "R37") (pin "1") (pinfunction "1_1") (pintype "passive"))
    )
  )
)
